# T03_MotionControledLamp.net
KiCad netlist of a schematic drawn in EAGLE
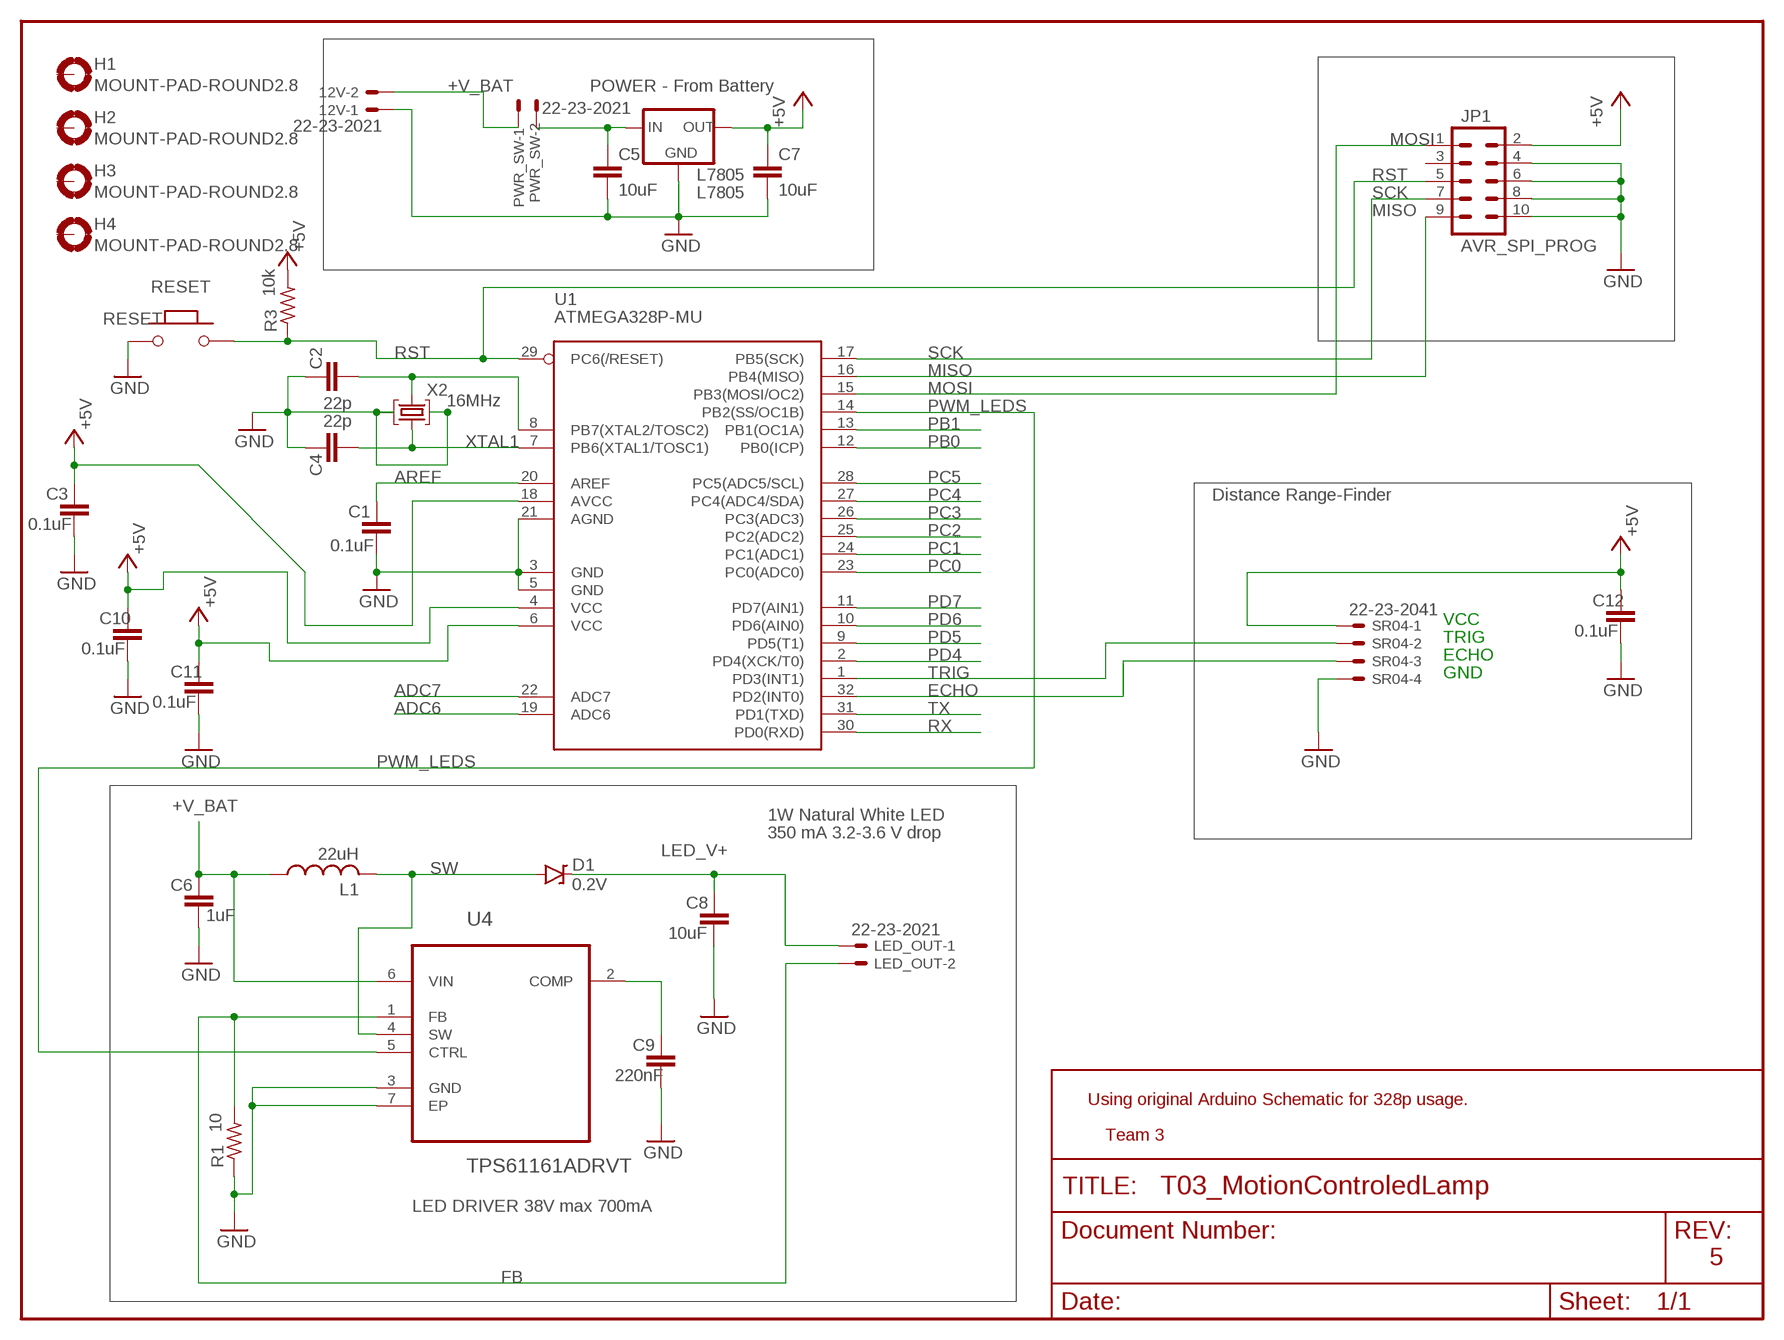
[diagram p0: schematic, sheet 1]

(export (version "E")
  (design (tool "Eeschema 10.0.6"))
  (components
    (comp (ref "12V")
      (value "22-23-2021")
      (footprint "eagle-import:22-23-2021")
      (fields (field (name "MF") "MOLEX"))
      (libsource (lib "eagle-import") (part "22-23-2021"))
    )
    (comp (ref "C1")
      (value "0.1uF")
      (footprint "eagle-import:C0603-ROUND")
      (libsource (lib "eagle-import") (part "C-EUC0603"))
    )
    (comp (ref "C2")
      (value "22p")
      (footprint "eagle-import:C0603-ROUND")
      (libsource (lib "eagle-import") (part "C-EUC0603"))
    )
    (comp (ref "C3")
      (value "0.1uF")
      (footprint "eagle-import:C0603-ROUND")
      (libsource (lib "eagle-import") (part "C-EUC0603"))
    )
    (comp (ref "C4")
      (value "22p")
      (footprint "eagle-import:C0603-ROUND")
      (libsource (lib "eagle-import") (part "C-EUC0603"))
    )
    (comp (ref "C5")
      (value "10uF")
      (footprint "eagle-import:C1206")
      (libsource (lib "eagle-import") (part "rcl_C-EUC1206"))
    )
    (comp (ref "C6")
      (value "1uF")
      (footprint "eagle-import:C0603-ROUND")
      (libsource (lib "eagle-import") (part "C-EUC0603"))
    )
    (comp (ref "C7")
      (value "10uF")
      (footprint "eagle-import:C1206")
      (libsource (lib "eagle-import") (part "rcl_C-EUC1206"))
    )
    (comp (ref "C8")
      (value "10uF")
      (footprint "eagle-import:C0603-ROUND")
      (libsource (lib "eagle-import") (part "C-EUC0603"))
    )
    (comp (ref "C9")
      (value "220nF")
      (footprint "eagle-import:C0603-ROUND")
      (libsource (lib "eagle-import") (part "C-EUC0603"))
    )
    (comp (ref "C10")
      (value "0.1uF")
      (footprint "eagle-import:C0603-ROUND")
      (libsource (lib "eagle-import") (part "C-EUC0603"))
    )
    (comp (ref "C11")
      (value "0.1uF")
      (footprint "eagle-import:C0603-ROUND")
      (libsource (lib "eagle-import") (part "C-EUC0603"))
    )
    (comp (ref "C12")
      (value "0.1uF")
      (footprint "eagle-import:C0603-ROUND")
      (libsource (lib "eagle-import") (part "C-EUC0603"))
    )
    (comp (ref "D1")
      (value "0.2V")
      (footprint "eagle-import:SOD-323")
      (libsource (lib "eagle-import") (part "DIODE-ZENER3.3V"))
    )
    (comp (ref "H1")
      (value "MOUNT-PAD-ROUND2.8")
      (footprint "eagle-import:2,8-PAD")
      (libsource (lib "eagle-import") (part "MOUNT-PAD-ROUND2.8"))
    )
    (comp (ref "H2")
      (value "MOUNT-PAD-ROUND2.8")
      (footprint "eagle-import:2,8-PAD")
      (libsource (lib "eagle-import") (part "MOUNT-PAD-ROUND2.8"))
    )
    (comp (ref "H3")
      (value "MOUNT-PAD-ROUND2.8")
      (footprint "eagle-import:2,8-PAD")
      (libsource (lib "eagle-import") (part "MOUNT-PAD-ROUND2.8"))
    )
    (comp (ref "H4")
      (value "MOUNT-PAD-ROUND2.8")
      (footprint "eagle-import:2,8-PAD")
      (libsource (lib "eagle-import") (part "MOUNT-PAD-ROUND2.8"))
    )
    (comp (ref "JP1")
      (value "AVR_SPI_PROG")
      (footprint "eagle-import:2X5-SHROUDED_LOCK")
      (libsource (lib "eagle-import") (part "M05X2SHD_LOCK"))
    )
    (comp (ref "L1")
      (value "22uH")
      (footprint "eagle-import:L4532P")
      (libsource (lib "eagle-import") (part "L-USL4532P"))
    )
    (comp (ref "L7805")
      (value "L7805")
      (footprint "eagle-import:78XXL")
      (libsource (lib "eagle-import") (part "78XXL"))
    )
    (comp (ref "LED_OUT")
      (value "22-23-2021")
      (footprint "eagle-import:22-23-2021")
      (fields (field (name "MF") "MOLEX"))
      (libsource (lib "eagle-import") (part "22-23-2021"))
    )
    (comp (ref "PWR_SW")
      (value "22-23-2021")
      (footprint "eagle-import:22-23-2021")
      (fields (field (name "MF") "MOLEX"))
      (libsource (lib "eagle-import") (part "22-23-2021"))
    )
    (comp (ref "R1")
      (value "10")
      (footprint "eagle-import:M1206")
      (libsource (lib "eagle-import") (part "R-US_M1206"))
    )
    (comp (ref "R3")
      (value "10k")
      (footprint "eagle-import:M1206")
      (libsource (lib "eagle-import") (part "R-US_M1206"))
    )
    (comp (ref "RESET")
      (value "RESET")
      (footprint "eagle-import:SMD_157SW")
      (libsource (lib "eagle-import") (part "MYSMD_PB157"))
    )
    (comp (ref "SR04")
      (value "22-23-2041")
      (footprint "eagle-import:22-23-2041")
      (fields (field (name "MF") "MOLEX"))
      (libsource (lib "eagle-import") (part "22-23-2041"))
    )
    (comp (ref "U1")
      (value "ATMEGA328P-MU")
      (footprint "eagle-import:TQFP32-08")
      (libsource (lib "eagle-import") (part "ATMEGAXX8-AU"))
    )
    (comp (ref "U4")
      (value "TPS61161ADRVT")
      (footprint "eagle-import:SON65P200X200X80-7N")
      (libsource (lib "eagle-import") (part "TPS61161ADRVT"))
    )
    (comp (ref "X2")
      (value "16MHz")
      (footprint "eagle-import:CRYSTAL-3.2-2.5")
      (libsource (lib "eagle-import") (part "CRYSTAL-3.2-2.5"))
    )
  )
  (nets
    (net (code "1") (name "+5V") (class "Default")
      (node (ref "C10") (pin "2") (pinfunction "2_2") (pintype "passive"))
      (node (ref "C11") (pin "2") (pinfunction "2_2") (pintype "passive"))
      (node (ref "C12") (pin "2") (pinfunction "2_2") (pintype "passive"))
      (node (ref "C3") (pin "2") (pinfunction "2_2") (pintype "passive"))
      (node (ref "C7") (pin "1") (pinfunction "1_1") (pintype "passive"))
      (node (ref "JP1") (pin "2") (pinfunction "2_2") (pintype "passive"))
      (node (ref "L7805") (pin "OUT") (pinfunction "OUT_OUT") (pintype "passive"))
      (node (ref "R3") (pin "2") (pinfunction "2_2") (pintype "passive"))
      (node (ref "SR04") (pin "1") (pinfunction "S_1") (pintype "passive"))
      (node (ref "U1") (pin "18") (pinfunction "AVCC_18") (pintype "bidirectional"))
      (node (ref "U1") (pin "4") (pinfunction "VCC_4") (pintype "bidirectional"))
      (node (ref "U1") (pin "6") (pinfunction "VCC_6") (pintype "bidirectional"))
    )
    (net (code "2") (name "/+V_BAT") (class "Default")
      (node (ref "12V") (pin "2") (pinfunction "S_2") (pintype "passive"))
      (node (ref "C6") (pin "2") (pinfunction "2_2") (pintype "passive"))
      (node (ref "L1") (pin "1") (pinfunction "1_1") (pintype "passive"))
      (node (ref "PWR_SW") (pin "1") (pinfunction "S_1") (pintype "passive"))
      (node (ref "U4") (pin "6") (pinfunction "VIN_6") (pintype "power_in"))
    )
    (net (code "3") (name "/ADC6") (class "Default")
      (node (ref "U1") (pin "19") (pinfunction "ADC6_19") (pintype "bidirectional"))
    )
    (net (code "4") (name "/ADC7") (class "Default")
      (node (ref "U1") (pin "22") (pinfunction "ADC7_22") (pintype "bidirectional"))
    )
    (net (code "5") (name "/AREF") (class "Default")
      (node (ref "C1") (pin "2") (pinfunction "2_2") (pintype "passive"))
      (node (ref "U1") (pin "20") (pinfunction "AREF_20") (pintype "bidirectional"))
    )
    (net (code "6") (name "/ECHO") (class "Default")
      (node (ref "SR04") (pin "3") (pinfunction "S_3") (pintype "passive"))
      (node (ref "U1") (pin "32") (pinfunction "PD2(INT0)_32") (pintype "bidirectional"))
    )
    (net (code "7") (name "/FB") (class "Default")
      (node (ref "LED_OUT") (pin "2") (pinfunction "S_2") (pintype "passive"))
      (node (ref "R1") (pin "2") (pinfunction "2_2") (pintype "passive"))
      (node (ref "U4") (pin "1") (pinfunction "FB_1") (pintype "input"))
    )
    (net (code "8") (name "/LED_V+") (class "Default")
      (node (ref "C8") (pin "2") (pinfunction "2_2") (pintype "passive"))
      (node (ref "D1") (pin "C") (pinfunction "C_C") (pintype "passive"))
      (node (ref "LED_OUT") (pin "1") (pinfunction "S_1") (pintype "passive"))
    )
    (net (code "9") (name "/MISO") (class "Default")
      (node (ref "JP1") (pin "9") (pinfunction "9_9") (pintype "passive"))
      (node (ref "U1") (pin "16") (pinfunction "PB4(MISO)_16") (pintype "bidirectional"))
    )
    (net (code "10") (name "/MOSI") (class "Default")
      (node (ref "JP1") (pin "1") (pinfunction "1_1") (pintype "passive"))
      (node (ref "U1") (pin "15") (pinfunction "PB3(MOSI/OC2)_15") (pintype "bidirectional"))
    )
    (net (code "11") (name "/PB0") (class "Default")
      (node (ref "U1") (pin "12") (pinfunction "PB0(ICP)_12") (pintype "bidirectional"))
    )
    (net (code "12") (name "/PB1") (class "Default")
      (node (ref "U1") (pin "13") (pinfunction "PB1(OC1A)_13") (pintype "bidirectional"))
    )
    (net (code "13") (name "/PC0") (class "Default")
      (node (ref "U1") (pin "23") (pinfunction "PC0(ADC0)_23") (pintype "bidirectional"))
    )
    (net (code "14") (name "/PC1") (class "Default")
      (node (ref "U1") (pin "24") (pinfunction "PC1(ADC1)_24") (pintype "bidirectional"))
    )
    (net (code "15") (name "/PC2") (class "Default")
      (node (ref "U1") (pin "25") (pinfunction "PC2(ADC2)_25") (pintype "bidirectional"))
    )
    (net (code "16") (name "/PC3") (class "Default")
      (node (ref "U1") (pin "26") (pinfunction "PC3(ADC3)_26") (pintype "bidirectional"))
    )
    (net (code "17") (name "/PC4") (class "Default")
      (node (ref "U1") (pin "27") (pinfunction "PC4(ADC4/SDA)_27") (pintype "bidirectional"))
    )
    (net (code "18") (name "/PC5") (class "Default")
      (node (ref "U1") (pin "28") (pinfunction "PC5(ADC5/SCL)_28") (pintype "bidirectional"))
    )
    (net (code "19") (name "/PD4") (class "Default")
      (node (ref "U1") (pin "2") (pinfunction "PD4(XCK/T0)_2") (pintype "bidirectional"))
    )
    (net (code "20") (name "/PD5") (class "Default")
      (node (ref "U1") (pin "9") (pinfunction "PD5(T1)_9") (pintype "bidirectional"))
    )
    (net (code "21") (name "/PD6") (class "Default")
      (node (ref "U1") (pin "10") (pinfunction "PD6(AIN0)_10") (pintype "bidirectional"))
    )
    (net (code "22") (name "/PD7") (class "Default")
      (node (ref "U1") (pin "11") (pinfunction "PD7(AIN1)_11") (pintype "bidirectional"))
    )
    (net (code "23") (name "/PWM_LEDS") (class "Default")
      (node (ref "U1") (pin "14") (pinfunction "PB2(SS/OC1B)_14") (pintype "bidirectional"))
      (node (ref "U4") (pin "5") (pinfunction "CTRL_5") (pintype "input"))
    )
    (net (code "24") (name "/RST") (class "Default")
      (node (ref "JP1") (pin "5") (pinfunction "5_5") (pintype "passive"))
      (node (ref "R3") (pin "1") (pinfunction "1_1") (pintype "passive"))
      (node (ref "RESET") (pin "2") (pinfunction "2_2") (pintype "passive"))
      (node (ref "U1") (pin "29") (pinfunction "PC6(/RESET)_29") (pintype "bidirectional"))
    )
    (net (code "25") (name "/RX") (class "Default")
      (node (ref "U1") (pin "30") (pinfunction "PD0(RXD)_30") (pintype "bidirectional"))
    )
    (net (code "26") (name "/SCK") (class "Default")
      (node (ref "JP1") (pin "7") (pinfunction "7_7") (pintype "passive"))
      (node (ref "U1") (pin "17") (pinfunction "PB5(SCK)_17") (pintype "bidirectional"))
    )
    (net (code "27") (name "/SW") (class "Default")
      (node (ref "D1") (pin "A") (pinfunction "A_A") (pintype "passive"))
      (node (ref "L1") (pin "2") (pinfunction "2_2") (pintype "passive"))
      (node (ref "U4") (pin "4") (pinfunction "SW_4") (pintype "input"))
    )
    (net (code "28") (name "/TRIG") (class "Default")
      (node (ref "SR04") (pin "2") (pinfunction "S_2") (pintype "passive"))
      (node (ref "U1") (pin "1") (pinfunction "PD3(INT1)_1") (pintype "bidirectional"))
    )
    (net (code "29") (name "/TX") (class "Default")
      (node (ref "U1") (pin "31") (pinfunction "PD1(TXD)_31") (pintype "bidirectional"))
    )
    (net (code "30") (name "/XTAL1") (class "Default")
      (node (ref "C4") (pin "1") (pinfunction "1_1") (pintype "passive"))
      (node (ref "U1") (pin "7") (pinfunction "PB6(XTAL1/TOSC1)_7") (pintype "bidirectional"))
      (node (ref "X2") (pin "1") (pinfunction "C1_1") (pintype "passive"))
    )
    (net (code "31") (name "GND") (class "Default")
      (node (ref "12V") (pin "1") (pinfunction "S_1") (pintype "passive"))
      (node (ref "C1") (pin "1") (pinfunction "1_1") (pintype "passive"))
      (node (ref "C10") (pin "1") (pinfunction "1_1") (pintype "passive"))
      (node (ref "C11") (pin "1") (pinfunction "1_1") (pintype "passive"))
      (node (ref "C12") (pin "1") (pinfunction "1_1") (pintype "passive"))
      (node (ref "C2") (pin "2") (pinfunction "2_2") (pintype "passive"))
      (node (ref "C3") (pin "1") (pinfunction "1_1") (pintype "passive"))
      (node (ref "C4") (pin "2") (pinfunction "2_2") (pintype "passive"))
      (node (ref "C5") (pin "2") (pinfunction "2_2") (pintype "passive"))
      (node (ref "C6") (pin "1") (pinfunction "1_1") (pintype "passive"))
      (node (ref "C7") (pin "2") (pinfunction "2_2") (pintype "passive"))
      (node (ref "C8") (pin "1") (pinfunction "1_1") (pintype "passive"))
      (node (ref "C9") (pin "1") (pinfunction "1_1") (pintype "passive"))
      (node (ref "JP1") (pin "10") (pinfunction "10_10") (pintype "passive"))
      (node (ref "JP1") (pin "4") (pinfunction "4_4") (pintype "passive"))
      (node (ref "JP1") (pin "6") (pinfunction "6_6") (pintype "passive"))
      (node (ref "JP1") (pin "8") (pinfunction "8_8") (pintype "passive"))
      (node (ref "L7805") (pin "GND") (pinfunction "GND_GND") (pintype "input"))
      (node (ref "R1") (pin "1") (pinfunction "1_1") (pintype "passive"))
      (node (ref "RESET") (pin "1") (pinfunction "1_1") (pintype "passive"))
      (node (ref "SR04") (pin "4") (pinfunction "S_4") (pintype "passive"))
      (node (ref "U1") (pin "21") (pinfunction "AGND_21") (pintype "bidirectional"))
      (node (ref "U1") (pin "3") (pinfunction "GND_3") (pintype "bidirectional"))
      (node (ref "U1") (pin "5") (pinfunction "GND_5") (pintype "bidirectional"))
      (node (ref "U4") (pin "3") (pinfunction "GND_3") (pintype "passive"))
      (node (ref "U4") (pin "7") (pinfunction "EP_7") (pintype "passive"))
      (node (ref "X2") (pin "2") (pinfunction "GND_2") (pintype "passive"))
      (node (ref "X2") (pin "4") (pinfunction "GND_4") (pintype "passive"))
    )
    (net (code "32") (name "Net-(PWR_SWB-S)") (class "Default")
      (node (ref "C5") (pin "1") (pinfunction "1_1") (pintype "passive"))
      (node (ref "L7805") (pin "IN") (pinfunction "IN_IN") (pintype "input"))
      (node (ref "PWR_SW") (pin "2") (pinfunction "S_2") (pintype "passive"))
    )
    (net (code "33") (name "Net-(U1-PB7(XTAL2{slash}TOSC2))") (class "Default")
      (node (ref "C2") (pin "1") (pinfunction "1_1") (pintype "passive"))
      (node (ref "U1") (pin "8") (pinfunction "PB7(XTAL2/TOSC2)_8") (pintype "bidirectional"))
      (node (ref "X2") (pin "3") (pinfunction "C2_3") (pintype "passive"))
    )
    (net (code "34") (name "Net-(U4-COMP)") (class "Default")
      (node (ref "C9") (pin "2") (pinfunction "2_2") (pintype "passive"))
      (node (ref "U4") (pin "2") (pinfunction "COMP_2") (pintype "output"))
    )
    (net (code "35") (name "unconnected-(H1-MOUNT-PadB2,8)") (class "Default")
      (node (ref "H1") (pin "B2,8") (pinfunction "MOUNT_B2,8") (pintype "passive"))
    )
    (net (code "36") (name "unconnected-(H2-MOUNT-PadB2,8)") (class "Default")
      (node (ref "H2") (pin "B2,8") (pinfunction "MOUNT_B2,8") (pintype "passive"))
    )
    (net (code "37") (name "unconnected-(H3-MOUNT-PadB2,8)") (class "Default")
      (node (ref "H3") (pin "B2,8") (pinfunction "MOUNT_B2,8") (pintype "passive"))
    )
    (net (code "38") (name "unconnected-(H4-MOUNT-PadB2,8)") (class "Default")
      (node (ref "H4") (pin "B2,8") (pinfunction "MOUNT_B2,8") (pintype "passive"))
    )
    (net (code "39") (name "unconnected-(JP1-Pad3)") (class "Default")
      (node (ref "JP1") (pin "3") (pinfunction "3_3") (pintype "passive"))
    )
  )
)
